# AUX_Analog_IO.net
KiCad netlist of a schematic drawn in Altium Designer
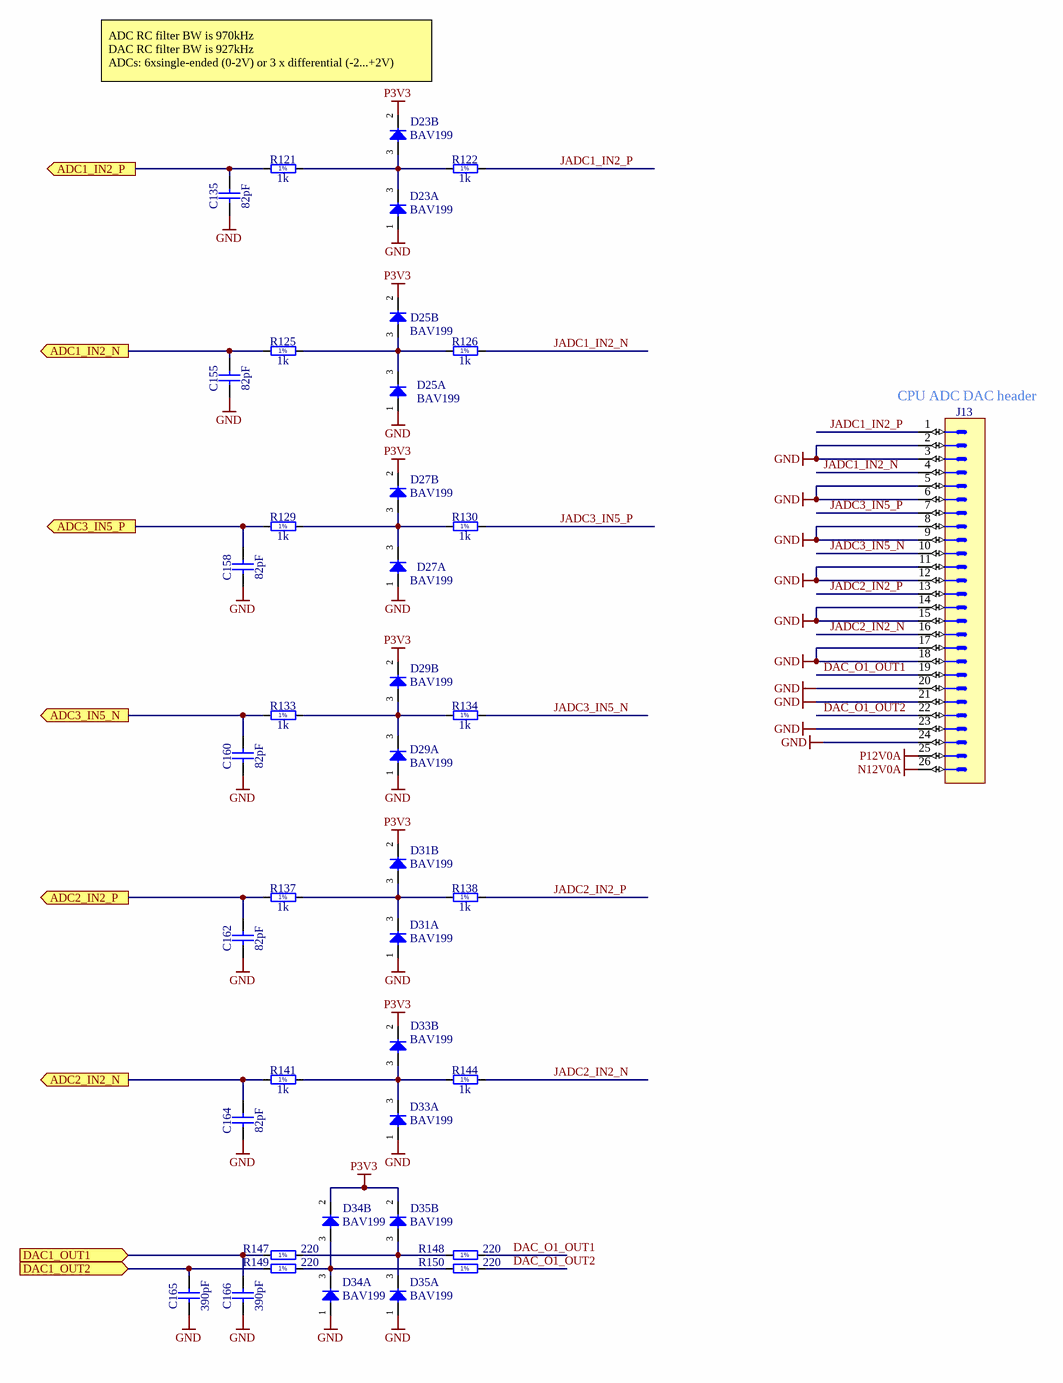
[diagram p0: AUX_Analog_IO.SchDoc]

(export (version "E")
  (design (tool "Eeschema 10.0.6"))
  (components
    (comp (ref "C135")
      (value "82pF")
      (footprint "CAPC1608X87N")
      (description "Non-polarised capacitor")
      (fields
        (field (name "PART NUMBER") "CC0603_82PF_50V_5%_NP0")
        (field (name "VOLTAGE") "50V")
        (field (name "AUTHOR") "CERN DEM JLC")
      )
      (libsource (lib "Capacitors") (part "Capacitor - non polarized"))
    )
    (comp (ref "C155")
      (value "82pF")
      (footprint "CAPC1608X87N")
      (description "Non-polarised capacitor")
      (fields
        (field (name "PART NUMBER") "CC0603_82PF_50V_5%_NP0")
        (field (name "VOLTAGE") "50V")
        (field (name "AUTHOR") "CERN DEM JLC")
      )
      (libsource (lib "Capacitors") (part "Capacitor - non polarized"))
    )
    (comp (ref "C158")
      (value "82pF")
      (footprint "CAPC1608X87N")
      (description "Non-polarised capacitor")
      (fields
        (field (name "PART NUMBER") "CC0603_82PF_50V_5%_NP0")
        (field (name "VOLTAGE") "50V")
        (field (name "AUTHOR") "CERN DEM JLC")
      )
      (libsource (lib "Capacitors") (part "Capacitor - non polarized"))
    )
    (comp (ref "C160")
      (value "82pF")
      (footprint "CAPC1608X87N")
      (description "Non-polarised capacitor")
      (fields
        (field (name "PART NUMBER") "CC0603_82PF_50V_5%_NP0")
        (field (name "VOLTAGE") "50V")
        (field (name "AUTHOR") "CERN DEM JLC")
      )
      (libsource (lib "Capacitors") (part "Capacitor - non polarized"))
    )
    (comp (ref "C162")
      (value "82pF")
      (footprint "CAPC1608X87N")
      (description "Non-polarised capacitor")
      (fields
        (field (name "PART NUMBER") "CC0603_82PF_50V_5%_NP0")
        (field (name "VOLTAGE") "50V")
        (field (name "AUTHOR") "CERN DEM JLC")
      )
      (libsource (lib "Capacitors") (part "Capacitor - non polarized"))
    )
    (comp (ref "C164")
      (value "82pF")
      (footprint "CAPC1608X87N")
      (description "Non-polarised capacitor")
      (fields
        (field (name "PART NUMBER") "CC0603_82PF_50V_5%_NP0")
        (field (name "VOLTAGE") "50V")
        (field (name "AUTHOR") "CERN DEM JLC")
      )
      (libsource (lib "Capacitors") (part "Capacitor - non polarized"))
    )
    (comp (ref "C165")
      (value "390pF")
      (footprint "CAPC1608X87N")
      (description "Non-polarised capacitor")
      (fields
        (field (name "PART NUMBER") "CC0603_390PF_50V_5%_NP0")
        (field (name "VOLTAGE") "50V")
        (field (name "AUTHOR") "CERN DEM JLC")
      )
      (libsource (lib "Capacitors") (part "Capacitor - non polarized"))
    )
    (comp (ref "C166")
      (value "390pF")
      (footprint "CAPC1608X87N")
      (description "Non-polarised capacitor")
      (fields
        (field (name "PART NUMBER") "CC0603_390PF_50V_5%_NP0")
        (field (name "VOLTAGE") "50V")
        (field (name "AUTHOR") "CERN DEM JLC")
      )
      (libsource (lib "Capacitors") (part "Capacitor - non polarized"))
    )
    (comp (ref "D23")
      (value "BAV199")
      (footprint "SOT95P240X110-3N")
      (description "Serial Diode")
      (fields
        (field (name "VOLTAGE") "75V")
        (field (name "POWER") "250mW")
        (field (name "AUTHOR") "CERN DEM JMW")
      )
      (libsource (lib "ICs And Semiconductors") (part "Diode x2 A1C3_A3C2"))
    )
    (comp (ref "D25")
      (value "BAV199")
      (footprint "SOT95P240X110-3N")
      (description "Serial Diode")
      (fields
        (field (name "VOLTAGE") "75V")
        (field (name "POWER") "250mW")
        (field (name "AUTHOR") "CERN DEM JMW")
      )
      (libsource (lib "ICs And Semiconductors") (part "Diode x2 A1C3_A3C2"))
    )
    (comp (ref "D27")
      (value "BAV199")
      (footprint "SOT95P240X110-3N")
      (description "Serial Diode")
      (fields
        (field (name "VOLTAGE") "75V")
        (field (name "POWER") "250mW")
        (field (name "AUTHOR") "CERN DEM JMW")
      )
      (libsource (lib "ICs And Semiconductors") (part "Diode x2 A1C3_A3C2"))
    )
    (comp (ref "D29")
      (value "BAV199")
      (footprint "SOT95P240X110-3N")
      (description "Serial Diode")
      (fields
        (field (name "VOLTAGE") "75V")
        (field (name "POWER") "250mW")
        (field (name "AUTHOR") "CERN DEM JMW")
      )
      (libsource (lib "ICs And Semiconductors") (part "Diode x2 A1C3_A3C2"))
    )
    (comp (ref "D31")
      (value "BAV199")
      (footprint "SOT95P240X110-3N")
      (description "Serial Diode")
      (fields
        (field (name "VOLTAGE") "75V")
        (field (name "POWER") "250mW")
        (field (name "AUTHOR") "CERN DEM JMW")
      )
      (libsource (lib "ICs And Semiconductors") (part "Diode x2 A1C3_A3C2"))
    )
    (comp (ref "D33")
      (value "BAV199")
      (footprint "SOT95P240X110-3N")
      (description "Serial Diode")
      (fields
        (field (name "VOLTAGE") "75V")
        (field (name "POWER") "250mW")
        (field (name "AUTHOR") "CERN DEM JMW")
      )
      (libsource (lib "ICs And Semiconductors") (part "Diode x2 A1C3_A3C2"))
    )
    (comp (ref "D34")
      (value "BAV199")
      (footprint "SOT95P240X110-3N")
      (description "Serial Diode")
      (fields
        (field (name "VOLTAGE") "75V")
        (field (name "POWER") "250mW")
        (field (name "AUTHOR") "CERN DEM JMW")
      )
      (libsource (lib "ICs And Semiconductors") (part "Diode x2 A1C3_A3C2"))
    )
    (comp (ref "D35")
      (value "BAV199")
      (footprint "SOT95P240X110-3N")
      (description "Serial Diode")
      (fields
        (field (name "VOLTAGE") "75V")
        (field (name "POWER") "250mW")
        (field (name "AUTHOR") "CERN DEM JMW")
      )
      (libsource (lib "ICs And Semiconductors") (part "Diode x2 A1C3_A3C2"))
    )
    (comp (ref "J13")
      (value "Header 26")
      (footprint "3M_N2526-6002RB")
      (description "Connector 26 Male")
      (fields
        (field (name "PART NUMBER") "3M_N2526-6002RB")
        (field (name "MANUFACTURER") "3M")
        (field (name "AUTHOR") "CERN DEM JLC")
      )
      (libsource (lib "Connectors") (part "Connector 26 Male"))
    )
    (comp (ref "R121")
      (value "1k")
      (footprint "RESC1005X40N")
      (description "Resistor - 1%")
      (fields
        (field (name "PART NUMBER") "R0402_1K_1%_0.0625W_100PPM")
        (field (name "POWER") "0.0625W")
        (field (name "AUTHOR") "CERN DEM JLC")
      )
      (libsource (lib "Resistors") (part "Resistor - 1%"))
    )
    (comp (ref "R122")
      (value "1k")
      (footprint "RESC1005X40N")
      (description "Resistor - 1%")
      (fields
        (field (name "PART NUMBER") "R0402_1K_1%_0.0625W_100PPM")
        (field (name "POWER") "0.0625W")
        (field (name "AUTHOR") "CERN DEM JLC")
      )
      (libsource (lib "Resistors") (part "Resistor - 1%"))
    )
    (comp (ref "R125")
      (value "1k")
      (footprint "RESC1005X40N")
      (description "Resistor - 1%")
      (fields
        (field (name "PART NUMBER") "R0402_1K_1%_0.0625W_100PPM")
        (field (name "POWER") "0.0625W")
        (field (name "AUTHOR") "CERN DEM JLC")
      )
      (libsource (lib "Resistors") (part "Resistor - 1%"))
    )
    (comp (ref "R126")
      (value "1k")
      (footprint "RESC1005X40N")
      (description "Resistor - 1%")
      (fields
        (field (name "PART NUMBER") "R0402_1K_1%_0.0625W_100PPM")
        (field (name "POWER") "0.0625W")
        (field (name "AUTHOR") "CERN DEM JLC")
      )
      (libsource (lib "Resistors") (part "Resistor - 1%"))
    )
    (comp (ref "R129")
      (value "1k")
      (footprint "RESC1005X40N")
      (description "Resistor - 1%")
      (fields
        (field (name "PART NUMBER") "R0402_1K_1%_0.0625W_100PPM")
        (field (name "POWER") "0.0625W")
        (field (name "AUTHOR") "CERN DEM JLC")
      )
      (libsource (lib "Resistors") (part "Resistor - 1%"))
    )
    (comp (ref "R130")
      (value "1k")
      (footprint "RESC1005X40N")
      (description "Resistor - 1%")
      (fields
        (field (name "PART NUMBER") "R0402_1K_1%_0.0625W_100PPM")
        (field (name "POWER") "0.0625W")
        (field (name "AUTHOR") "CERN DEM JLC")
      )
      (libsource (lib "Resistors") (part "Resistor - 1%"))
    )
    (comp (ref "R133")
      (value "1k")
      (footprint "RESC1005X40N")
      (description "Resistor - 1%")
      (fields
        (field (name "PART NUMBER") "R0402_1K_1%_0.0625W_100PPM")
        (field (name "POWER") "0.0625W")
        (field (name "AUTHOR") "CERN DEM JLC")
      )
      (libsource (lib "Resistors") (part "Resistor - 1%"))
    )
    (comp (ref "R134")
      (value "1k")
      (footprint "RESC1005X40N")
      (description "Resistor - 1%")
      (fields
        (field (name "PART NUMBER") "R0402_1K_1%_0.0625W_100PPM")
        (field (name "POWER") "0.0625W")
        (field (name "AUTHOR") "CERN DEM JLC")
      )
      (libsource (lib "Resistors") (part "Resistor - 1%"))
    )
    (comp (ref "R137")
      (value "1k")
      (footprint "RESC1005X40N")
      (description "Resistor - 1%")
      (fields
        (field (name "PART NUMBER") "R0402_1K_1%_0.0625W_100PPM")
        (field (name "POWER") "0.0625W")
        (field (name "AUTHOR") "CERN DEM JLC")
      )
      (libsource (lib "Resistors") (part "Resistor - 1%"))
    )
    (comp (ref "R138")
      (value "1k")
      (footprint "RESC1005X40N")
      (description "Resistor - 1%")
      (fields
        (field (name "PART NUMBER") "R0402_1K_1%_0.0625W_100PPM")
        (field (name "POWER") "0.0625W")
        (field (name "AUTHOR") "CERN DEM JLC")
      )
      (libsource (lib "Resistors") (part "Resistor - 1%"))
    )
    (comp (ref "R141")
      (value "1k")
      (footprint "RESC1005X40N")
      (description "Resistor - 1%")
      (fields
        (field (name "PART NUMBER") "R0402_1K_1%_0.0625W_100PPM")
        (field (name "POWER") "0.0625W")
        (field (name "AUTHOR") "CERN DEM JLC")
      )
      (libsource (lib "Resistors") (part "Resistor - 1%"))
    )
    (comp (ref "R144")
      (value "1k")
      (footprint "RESC1005X40N")
      (description "Resistor - 1%")
      (fields
        (field (name "PART NUMBER") "R0402_1K_1%_0.0625W_100PPM")
        (field (name "POWER") "0.0625W")
        (field (name "AUTHOR") "CERN DEM JLC")
      )
      (libsource (lib "Resistors") (part "Resistor - 1%"))
    )
    (comp (ref "R147")
      (value "220")
      (footprint "RESC1608X55N")
      (description "Resistor - 1%")
      (fields
        (field (name "PART NUMBER") "R0603_220R_1%_0.1W_100PPM")
        (field (name "POWER") "0.1W")
        (field (name "AUTHOR") "CERN DEM JLC")
      )
      (libsource (lib "Resistors") (part "Resistor - 1%"))
    )
    (comp (ref "R148")
      (value "220")
      (footprint "RESC1608X55N")
      (description "Resistor - 1%")
      (fields
        (field (name "PART NUMBER") "R0603_220R_1%_0.1W_100PPM")
        (field (name "POWER") "0.1W")
        (field (name "AUTHOR") "CERN DEM JLC")
      )
      (libsource (lib "Resistors") (part "Resistor - 1%"))
    )
    (comp (ref "R149")
      (value "220")
      (footprint "RESC1608X55N")
      (description "Resistor - 1%")
      (fields
        (field (name "PART NUMBER") "R0603_220R_1%_0.1W_100PPM")
        (field (name "POWER") "0.1W")
        (field (name "AUTHOR") "CERN DEM JLC")
      )
      (libsource (lib "Resistors") (part "Resistor - 1%"))
    )
    (comp (ref "R150")
      (value "220")
      (footprint "RESC1608X55N")
      (description "Resistor - 1%")
      (fields
        (field (name "PART NUMBER") "R0603_220R_1%_0.1W_100PPM")
        (field (name "POWER") "0.1W")
        (field (name "AUTHOR") "CERN DEM JLC")
      )
      (libsource (lib "Resistors") (part "Resistor - 1%"))
    )
  )
  (nets
    (net (code "1") (name "/ADC1_IN2_N") (class "Default")
      (node (ref "C155") (pin "2") (pinfunction "2_2") (pintype "passive"))
      (node (ref "R125") (pin "1") (pinfunction "1_1") (pintype "passive"))
    )
    (net (code "2") (name "/ADC1_IN2_P") (class "Default")
      (node (ref "C135") (pin "2") (pinfunction "2_2") (pintype "passive"))
      (node (ref "R121") (pin "1") (pinfunction "1_1") (pintype "passive"))
    )
    (net (code "3") (name "/ADC2_IN2_N") (class "Default")
      (node (ref "C164") (pin "2") (pinfunction "2_2") (pintype "passive"))
      (node (ref "R141") (pin "1") (pinfunction "1_1") (pintype "passive"))
    )
    (net (code "4") (name "/ADC2_IN2_P") (class "Default")
      (node (ref "C162") (pin "2") (pinfunction "2_2") (pintype "passive"))
      (node (ref "R137") (pin "1") (pinfunction "1_1") (pintype "passive"))
    )
    (net (code "5") (name "/ADC3_IN5_N") (class "Default")
      (node (ref "C160") (pin "2") (pinfunction "2_2") (pintype "passive"))
      (node (ref "R133") (pin "1") (pinfunction "1_1") (pintype "passive"))
    )
    (net (code "6") (name "/ADC3_IN5_P") (class "Default")
      (node (ref "C158") (pin "2") (pinfunction "2_2") (pintype "passive"))
      (node (ref "R129") (pin "1") (pinfunction "1_1") (pintype "passive"))
    )
    (net (code "7") (name "/DAC1_OUT1") (class "Default")
      (node (ref "C166") (pin "2") (pinfunction "2_2") (pintype "passive"))
      (node (ref "R147") (pin "1") (pinfunction "1_1") (pintype "passive"))
    )
    (net (code "8") (name "/DAC1_OUT2") (class "Default")
      (node (ref "C165") (pin "2") (pinfunction "2_2") (pintype "passive"))
      (node (ref "R149") (pin "1") (pinfunction "1_1") (pintype "passive"))
    )
    (net (code "9") (name "/DAC_O1_OUT1") (class "Default")
      (node (ref "J13") (pin "19") (pinfunction "19_19") (pintype "bidirectional"))
      (node (ref "R148") (pin "2") (pinfunction "2_2") (pintype "passive"))
    )
    (net (code "10") (name "/DAC_O1_OUT2") (class "Default")
      (node (ref "J13") (pin "22") (pinfunction "22_22") (pintype "bidirectional"))
      (node (ref "R150") (pin "2") (pinfunction "2_2") (pintype "passive"))
    )
    (net (code "11") (name "/JADC1_IN2_N") (class "Default")
      (node (ref "J13") (pin "4") (pinfunction "4_4") (pintype "bidirectional"))
      (node (ref "R126") (pin "2") (pinfunction "2_2") (pintype "passive"))
    )
    (net (code "12") (name "/JADC1_IN2_P") (class "Default")
      (node (ref "J13") (pin "1") (pinfunction "1_1") (pintype "bidirectional"))
      (node (ref "R122") (pin "2") (pinfunction "2_2") (pintype "passive"))
    )
    (net (code "13") (name "/JADC2_IN2_N") (class "Default")
      (node (ref "J13") (pin "16") (pinfunction "16_16") (pintype "bidirectional"))
      (node (ref "R144") (pin "2") (pinfunction "2_2") (pintype "passive"))
    )
    (net (code "14") (name "/JADC2_IN2_P") (class "Default")
      (node (ref "J13") (pin "13") (pinfunction "13_13") (pintype "bidirectional"))
      (node (ref "R138") (pin "2") (pinfunction "2_2") (pintype "passive"))
    )
    (net (code "15") (name "/JADC3_IN5_N") (class "Default")
      (node (ref "J13") (pin "10") (pinfunction "10_10") (pintype "bidirectional"))
      (node (ref "R134") (pin "2") (pinfunction "2_2") (pintype "passive"))
    )
    (net (code "16") (name "/JADC3_IN5_P") (class "Default")
      (node (ref "J13") (pin "7") (pinfunction "7_7") (pintype "bidirectional"))
      (node (ref "R130") (pin "2") (pinfunction "2_2") (pintype "passive"))
    )
    (net (code "17") (name "GND") (class "Default")
      (node (ref "C135") (pin "1") (pinfunction "1_1") (pintype "passive"))
      (node (ref "C155") (pin "1") (pinfunction "1_1") (pintype "passive"))
      (node (ref "C158") (pin "1") (pinfunction "1_1") (pintype "passive"))
      (node (ref "C160") (pin "1") (pinfunction "1_1") (pintype "passive"))
      (node (ref "C162") (pin "1") (pinfunction "1_1") (pintype "passive"))
      (node (ref "C164") (pin "1") (pinfunction "1_1") (pintype "passive"))
      (node (ref "C165") (pin "1") (pinfunction "1_1") (pintype "passive"))
      (node (ref "C166") (pin "1") (pinfunction "1_1") (pintype "passive"))
      (node (ref "D23") (pin "1") (pinfunction "A_1") (pintype "passive"))
      (node (ref "D25") (pin "1") (pinfunction "A_1") (pintype "passive"))
      (node (ref "D27") (pin "1") (pinfunction "A_1") (pintype "passive"))
      (node (ref "D29") (pin "1") (pinfunction "A_1") (pintype "passive"))
      (node (ref "D31") (pin "1") (pinfunction "A_1") (pintype "passive"))
      (node (ref "D33") (pin "1") (pinfunction "A_1") (pintype "passive"))
      (node (ref "D34") (pin "1") (pinfunction "A_1") (pintype "passive"))
      (node (ref "D35") (pin "1") (pinfunction "A_1") (pintype "passive"))
      (node (ref "J13") (pin "11") (pinfunction "11_11") (pintype "bidirectional"))
      (node (ref "J13") (pin "12") (pinfunction "12_12") (pintype "bidirectional"))
      (node (ref "J13") (pin "14") (pinfunction "14_14") (pintype "bidirectional"))
      (node (ref "J13") (pin "15") (pinfunction "15_15") (pintype "bidirectional"))
      (node (ref "J13") (pin "17") (pinfunction "17_17") (pintype "bidirectional"))
      (node (ref "J13") (pin "18") (pinfunction "18_18") (pintype "bidirectional"))
      (node (ref "J13") (pin "2") (pinfunction "2_2") (pintype "bidirectional"))
      (node (ref "J13") (pin "20") (pinfunction "20_20") (pintype "bidirectional"))
      (node (ref "J13") (pin "21") (pinfunction "21_21") (pintype "bidirectional"))
      (node (ref "J13") (pin "23") (pinfunction "23_23") (pintype "bidirectional"))
      (node (ref "J13") (pin "24") (pinfunction "24_24") (pintype "bidirectional"))
      (node (ref "J13") (pin "3") (pinfunction "3_3") (pintype "bidirectional"))
      (node (ref "J13") (pin "5") (pinfunction "5_5") (pintype "bidirectional"))
      (node (ref "J13") (pin "6") (pinfunction "6_6") (pintype "bidirectional"))
      (node (ref "J13") (pin "8") (pinfunction "8_8") (pintype "bidirectional"))
      (node (ref "J13") (pin "9") (pinfunction "9_9") (pintype "bidirectional"))
    )
    (net (code "18") (name "N12V0A") (class "Default")
      (node (ref "J13") (pin "26") (pinfunction "26_26") (pintype "bidirectional"))
    )
    (net (code "19") (name "Net-(D23A-COMAC)") (class "Default")
      (node (ref "D23") (pin "3") (pinfunction "COMAC_3") (pintype "passive"))
      (node (ref "R121") (pin "2") (pinfunction "2_2") (pintype "passive"))
      (node (ref "R122") (pin "1") (pinfunction "1_1") (pintype "passive"))
    )
    (net (code "20") (name "Net-(D25A-COMAC)") (class "Default")
      (node (ref "D25") (pin "3") (pinfunction "COMAC_3") (pintype "passive"))
      (node (ref "R125") (pin "2") (pinfunction "2_2") (pintype "passive"))
      (node (ref "R126") (pin "1") (pinfunction "1_1") (pintype "passive"))
    )
    (net (code "21") (name "Net-(D27A-COMAC)") (class "Default")
      (node (ref "D27") (pin "3") (pinfunction "COMAC_3") (pintype "passive"))
      (node (ref "R129") (pin "2") (pinfunction "2_2") (pintype "passive"))
      (node (ref "R130") (pin "1") (pinfunction "1_1") (pintype "passive"))
    )
    (net (code "22") (name "Net-(D29A-COMAC)") (class "Default")
      (node (ref "D29") (pin "3") (pinfunction "COMAC_3") (pintype "passive"))
      (node (ref "R133") (pin "2") (pinfunction "2_2") (pintype "passive"))
      (node (ref "R134") (pin "1") (pinfunction "1_1") (pintype "passive"))
    )
    (net (code "23") (name "Net-(D31A-COMAC)") (class "Default")
      (node (ref "D31") (pin "3") (pinfunction "COMAC_3") (pintype "passive"))
      (node (ref "R137") (pin "2") (pinfunction "2_2") (pintype "passive"))
      (node (ref "R138") (pin "1") (pinfunction "1_1") (pintype "passive"))
    )
    (net (code "24") (name "Net-(D33A-COMAC)") (class "Default")
      (node (ref "D33") (pin "3") (pinfunction "COMAC_3") (pintype "passive"))
      (node (ref "R141") (pin "2") (pinfunction "2_2") (pintype "passive"))
      (node (ref "R144") (pin "1") (pinfunction "1_1") (pintype "passive"))
    )
    (net (code "25") (name "Net-(D34A-COMAC)") (class "Default")
      (node (ref "D34") (pin "3") (pinfunction "COMAC_3") (pintype "passive"))
      (node (ref "R149") (pin "2") (pinfunction "2_2") (pintype "passive"))
      (node (ref "R150") (pin "1") (pinfunction "1_1") (pintype "passive"))
    )
    (net (code "26") (name "Net-(D35A-COMAC)") (class "Default")
      (node (ref "D35") (pin "3") (pinfunction "COMAC_3") (pintype "passive"))
      (node (ref "R147") (pin "2") (pinfunction "2_2") (pintype "passive"))
      (node (ref "R148") (pin "1") (pinfunction "1_1") (pintype "passive"))
    )
    (net (code "27") (name "P3V3") (class "Default")
      (node (ref "D23") (pin "2") (pinfunction "C_2") (pintype "passive"))
      (node (ref "D25") (pin "2") (pinfunction "C_2") (pintype "passive"))
      (node (ref "D27") (pin "2") (pinfunction "C_2") (pintype "passive"))
      (node (ref "D29") (pin "2") (pinfunction "C_2") (pintype "passive"))
      (node (ref "D31") (pin "2") (pinfunction "C_2") (pintype "passive"))
      (node (ref "D33") (pin "2") (pinfunction "C_2") (pintype "passive"))
      (node (ref "D34") (pin "2") (pinfunction "C_2") (pintype "passive"))
      (node (ref "D35") (pin "2") (pinfunction "C_2") (pintype "passive"))
    )
    (net (code "28") (name "P12V0A") (class "Default")
      (node (ref "J13") (pin "25") (pinfunction "25_25") (pintype "bidirectional"))
    )
  )
)
